# SCH.net
KiCad netlist of a schematic drawn in Altium Designer
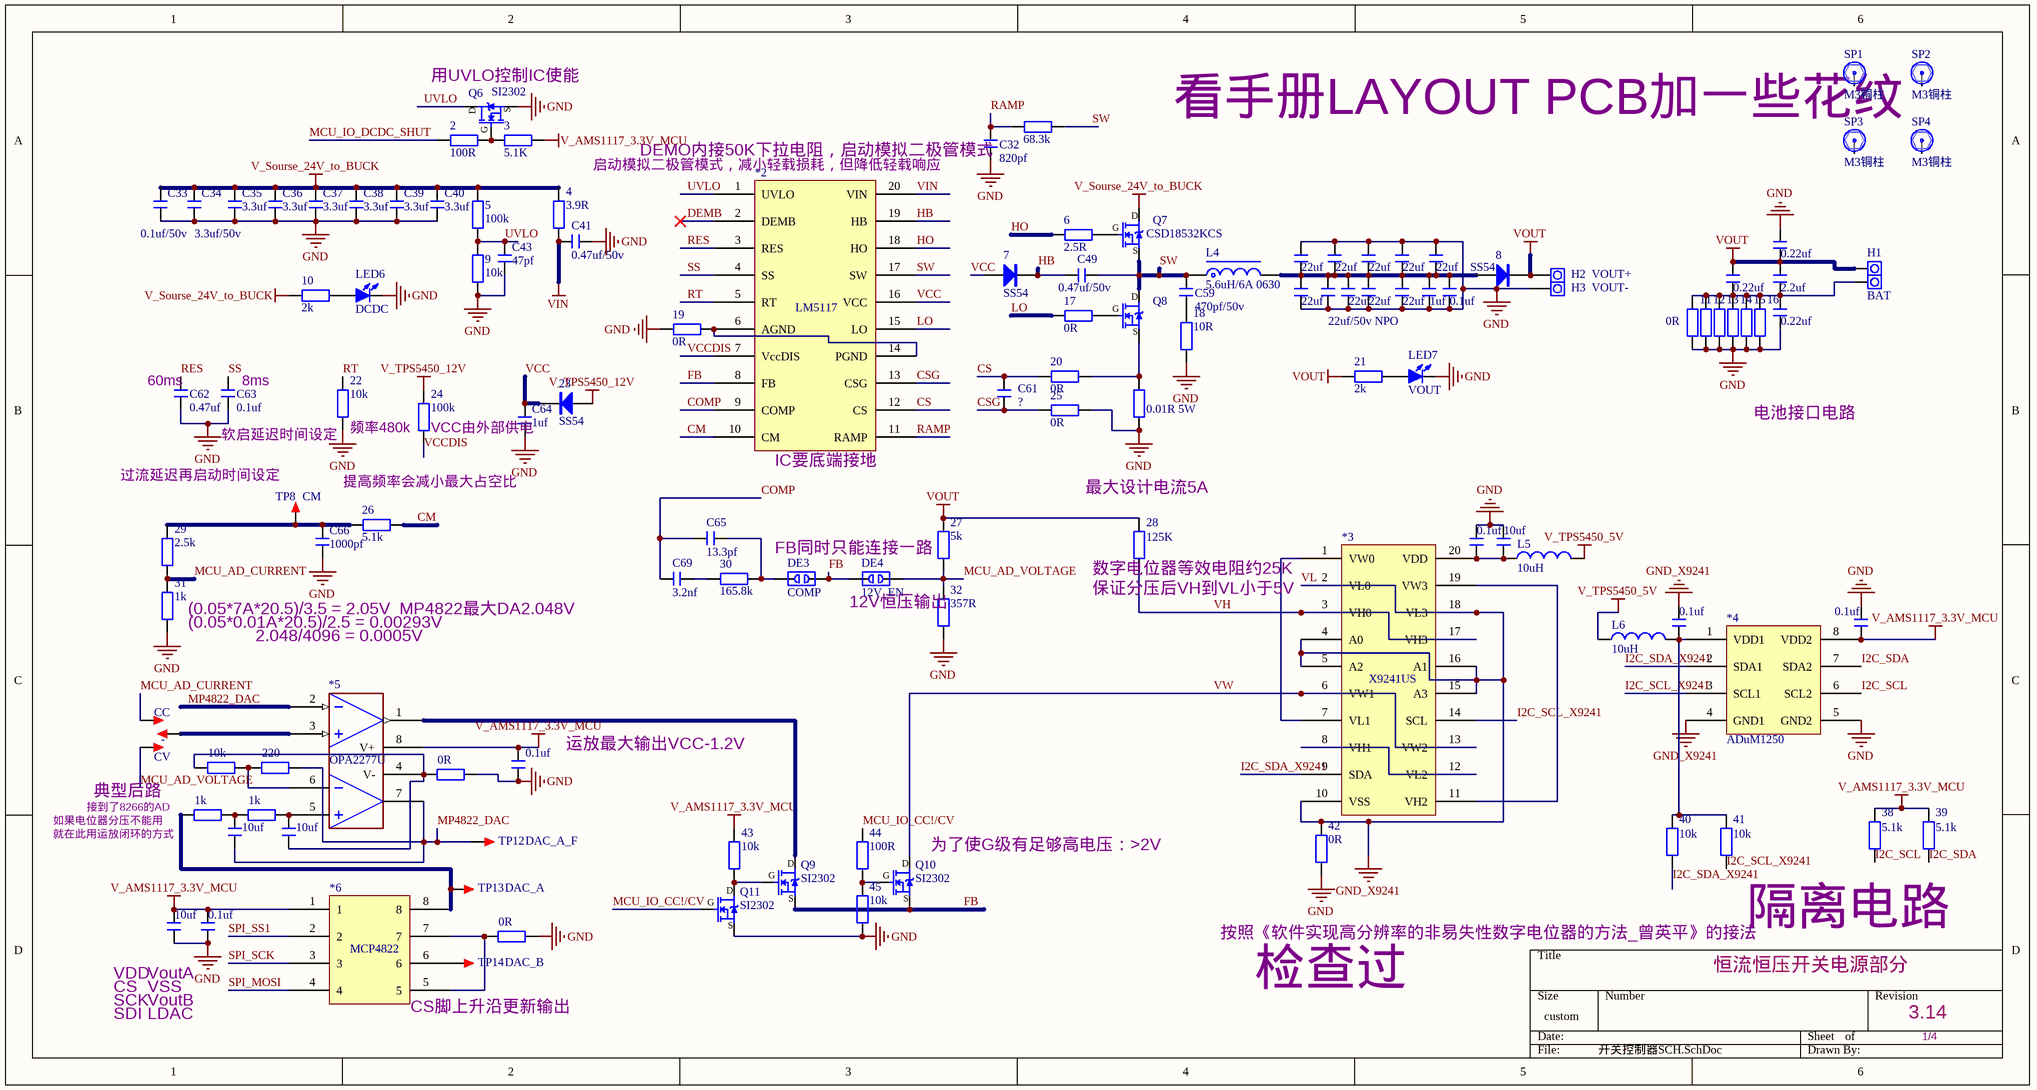
[diagram p0: 开关控制器SCH.SchDoc]

(export (version "E")
  (design (tool "Eeschema 10.0.6"))
  (components
    (comp (ref "*2") (value "LM5117") (footprint "SSOP20_M") (libsource (lib "IC_temp") (part "LM5117")))
    (comp (ref "*3") (value "X9241US") (footprint "SOP20_M") (libsource (lib "IC_temp") (part "X9241US")))
    (comp (ref "*4") (value "ADuM1250") (footprint "SOP8_N") (libsource (lib "IC_temp") (part "ADuM1250")))
    (comp (ref "*5") (value "OPA2277U") (footprint "SOP8_M") (libsource (lib "IC_temp") (part "OPA2277")))
    (comp (ref "*6") (value "MCP4822") (footprint "SOP8_M") (libsource (lib "IC_temp") (part "8")))
    (comp (ref "1")
      (value "68.3k")
      (footprint "R 0805_M")
      (description "贴片电阻")
      (libsource (lib "3.1   - 电阻-电容-电感") (part "R"))
    )
    (comp (ref "2")
      (value "100R")
      (footprint "R 0805_M")
      (description "贴片电阻")
      (libsource (lib "3.1   - 电阻-电容-电感") (part "R"))
    )
    (comp (ref "3")
      (value "5.1K")
      (footprint "R 0805_M")
      (description "贴片电阻")
      (libsource (lib "3.1   - 电阻-电容-电感") (part "R"))
    )
    (comp (ref "4")
      (value "3.9R")
      (footprint "R 0805_M")
      (description "贴片电阻")
      (libsource (lib "3.1   - 电阻-电容-电感") (part "R"))
    )
    (comp (ref "5")
      (value "100k")
      (footprint "R 0805_M")
      (description "贴片电阻")
      (libsource (lib "3.1   - 电阻-电容-电感") (part "R"))
    )
    (comp (ref "6")
      (value "2.5R")
      (footprint "R 0805_M")
      (description "贴片电阻")
      (libsource (lib "3.1   - 电阻-电容-电感") (part "R"))
    )
    (comp (ref "7")
      (value "SS54")
      (footprint "SMA")
      (description "肖特基二极管")
      (libsource (lib "8.1   - 二极管-整流桥") (part "SS34"))
    )
    (comp (ref "8")
      (value "SS54")
      (footprint "SMA")
      (description "肖特基二极管")
      (libsource (lib "8.1   - 二极管-整流桥") (part "SS34"))
    )
    (comp (ref "9")
      (value "10k")
      (footprint "R 0805_M")
      (description "贴片电阻")
      (libsource (lib "3.1   - 电阻-电容-电感") (part "R"))
    )
    (comp (ref "10")
      (value "2k")
      (footprint "R 0805_M")
      (description "贴片电阻")
      (libsource (lib "3.1   - 电阻-电容-电感") (part "R"))
    )
    (comp (ref "11")
      (value "0R")
      (footprint "R 0805_M")
      (description "贴片电阻")
      (libsource (lib "3.1   - 电阻-电容-电感") (part "R"))
    )
    (comp (ref "12")
      (value "0R")
      (footprint "R 0805_M")
      (description "贴片电阻")
      (libsource (lib "3.1   - 电阻-电容-电感") (part "R"))
    )
    (comp (ref "13")
      (value "0R")
      (footprint "R 0805_M")
      (description "贴片电阻")
      (libsource (lib "3.1   - 电阻-电容-电感") (part "R"))
    )
    (comp (ref "14")
      (value "0R")
      (footprint "R 0805_M")
      (description "贴片电阻")
      (libsource (lib "3.1   - 电阻-电容-电感") (part "R"))
    )
    (comp (ref "15")
      (value "0R")
      (footprint "R 0805_M")
      (description "贴片电阻")
      (libsource (lib "3.1   - 电阻-电容-电感") (part "R"))
    )
    (comp (ref "16")
      (value "0R")
      (footprint "R 0805_M")
      (description "贴片电阻")
      (libsource (lib "3.1   - 电阻-电容-电感") (part "R"))
    )
    (comp (ref "17")
      (value "0R")
      (footprint "R 0805_M")
      (description "贴片电阻")
      (libsource (lib "3.1   - 电阻-电容-电感") (part "R"))
    )
    (comp (ref "18")
      (value "10R")
      (footprint "R 0805_M")
      (description "贴片电阻")
      (libsource (lib "3.1   - 电阻-电容-电感") (part "R"))
    )
    (comp (ref "19")
      (value "0R")
      (footprint "R 0805_M")
      (description "贴片电阻")
      (libsource (lib "3.1   - 电阻-电容-电感") (part "R"))
    )
    (comp (ref "20")
      (value "0R")
      (footprint "R 0805_M")
      (description "贴片电阻")
      (libsource (lib "3.1   - 电阻-电容-电感") (part "R"))
    )
    (comp (ref "21")
      (value "2k")
      (footprint "R 0805_M")
      (description "贴片电阻")
      (libsource (lib "3.1   - 电阻-电容-电感") (part "R"))
    )
    (comp (ref "22")
      (value "10k")
      (footprint "R 0805_M")
      (description "贴片电阻")
      (libsource (lib "3.1   - 电阻-电容-电感") (part "R"))
    )
    (comp (ref "23")
      (value "SS54")
      (footprint "SMA")
      (description "肖特基二极管")
      (libsource (lib "8.1   - 二极管-整流桥") (part "SS34"))
    )
    (comp (ref "24")
      (value "100k")
      (footprint "R 0805_M")
      (description "贴片电阻")
      (libsource (lib "3.1   - 电阻-电容-电感") (part "R"))
    )
    (comp (ref "25")
      (value "0R")
      (footprint "R 0805_M")
      (description "贴片电阻")
      (libsource (lib "3.1   - 电阻-电容-电感") (part "R"))
    )
    (comp (ref "26")
      (value "5.1k")
      (footprint "R 0805_M")
      (description "贴片电阻")
      (libsource (lib "3.1   - 电阻-电容-电感") (part "R"))
    )
    (comp (ref "27")
      (value "5k")
      (footprint "R 0805_M")
      (description "贴片电阻")
      (libsource (lib "3.1   - 电阻-电容-电感") (part "R"))
    )
    (comp (ref "28")
      (value "125K")
      (footprint "R 0805_M")
      (description "贴片电阻")
      (libsource (lib "3.1   - 电阻-电容-电感") (part "R"))
    )
    (comp (ref "29")
      (value "2.5k")
      (footprint "R 0805_M")
      (description "贴片电阻")
      (libsource (lib "3.1   - 电阻-电容-电感") (part "R"))
    )
    (comp (ref "30")
      (value "165.8k")
      (footprint "R 0805_M")
      (description "贴片电阻")
      (libsource (lib "3.1   - 电阻-电容-电感") (part "R"))
    )
    (comp (ref "31")
      (value "1k")
      (footprint "R 0805_M")
      (description "贴片电阻")
      (libsource (lib "3.1   - 电阻-电容-电感") (part "R"))
    )
    (comp (ref "32")
      (value "357R")
      (footprint "R 0805_M")
      (description "贴片电阻")
      (libsource (lib "3.1   - 电阻-电容-电感") (part "R"))
    )
    (comp (ref "33")
      (value "10k")
      (footprint "R 0805_M")
      (description "贴片电阻")
      (libsource (lib "3.1   - 电阻-电容-电感") (part "R"))
    )
    (comp (ref "34")
      (value "220")
      (footprint "R 0805_M")
      (description "贴片电阻")
      (libsource (lib "3.1   - 电阻-电容-电感") (part "R"))
    )
    (comp (ref "35")
      (value "0R")
      (footprint "R 0805_M")
      (description "贴片电阻")
      (libsource (lib "3.1   - 电阻-电容-电感") (part "R"))
    )
    (comp (ref "36")
      (value "1k")
      (footprint "R 0805_M")
      (description "贴片电阻")
      (libsource (lib "3.1   - 电阻-电容-电感") (part "R"))
    )
    (comp (ref "37")
      (value "1k")
      (footprint "R 0805_M")
      (description "贴片电阻")
      (libsource (lib "3.1   - 电阻-电容-电感") (part "R"))
    )
    (comp (ref "38")
      (value "5.1k")
      (footprint "R 0805_M")
      (description "贴片电阻")
      (libsource (lib "3.1   - 电阻-电容-电感") (part "R"))
    )
    (comp (ref "39")
      (value "5.1k")
      (footprint "R 0805_M")
      (description "贴片电阻")
      (libsource (lib "3.1   - 电阻-电容-电感") (part "R"))
    )
    (comp (ref "40")
      (value "10k")
      (footprint "R 0805_M")
      (description "贴片电阻")
      (libsource (lib "3.1   - 电阻-电容-电感") (part "R"))
    )
    (comp (ref "41")
      (value "10k")
      (footprint "R 0805_M")
      (description "贴片电阻")
      (libsource (lib "3.1   - 电阻-电容-电感") (part "R"))
    )
    (comp (ref "42")
      (value "0R")
      (footprint "R 0805_M")
      (description "贴片电阻")
      (libsource (lib "3.1   - 电阻-电容-电感") (part "R"))
    )
    (comp (ref "43")
      (value "10k")
      (footprint "R 0805_M")
      (description "贴片电阻")
      (libsource (lib "3.1   - 电阻-电容-电感") (part "R"))
    )
    (comp (ref "44")
      (value "100R")
      (footprint "R 0805_M")
      (description "贴片电阻")
      (libsource (lib "3.1   - 电阻-电容-电感") (part "R"))
    )
    (comp (ref "45")
      (value "10k")
      (footprint "R 0805_M")
      (description "贴片电阻")
      (libsource (lib "3.1   - 电阻-电容-电感") (part "R"))
    )
    (comp (ref "46")
      (value "0R")
      (footprint "R 0805_M")
      (description "贴片电阻")
      (libsource (lib "3.1   - 电阻-电容-电感") (part "R"))
    )
    (comp (ref "C32")
      (value "820pf")
      (footprint "C 0805_M")
      (description "无极性贴片电容")
      (libsource (lib "3.1   - 电阻-电容-电感") (part "C"))
    )
    (comp (ref "C33")
      (value "0.1uf/50v")
      (footprint "C 0805_M")
      (description "无极性贴片电容")
      (libsource (lib "3.1   - 电阻-电容-电感") (part "C"))
    )
    (comp (ref "C34")
      (value "3.3uf/50v")
      (footprint "C 0805_M")
      (description "无极性贴片电容")
      (libsource (lib "3.1   - 电阻-电容-电感") (part "C"))
    )
    (comp (ref "C35")
      (value "3.3uf")
      (footprint "C 0805_M")
      (description "无极性贴片电容")
      (libsource (lib "3.1   - 电阻-电容-电感") (part "C"))
    )
    (comp (ref "C36")
      (value "3.3uf")
      (footprint "C 0805_M")
      (description "无极性贴片电容")
      (libsource (lib "3.1   - 电阻-电容-电感") (part "C"))
    )
    (comp (ref "C37")
      (value "3.3uf")
      (footprint "C 0805_M")
      (description "无极性贴片电容")
      (libsource (lib "3.1   - 电阻-电容-电感") (part "C"))
    )
    (comp (ref "C38")
      (value "3.3uf")
      (footprint "C 0805_M")
      (description "无极性贴片电容")
      (libsource (lib "3.1   - 电阻-电容-电感") (part "C"))
    )
    (comp (ref "C39")
      (value "3.3uf")
      (footprint "C 0805_M")
      (description "无极性贴片电容")
      (libsource (lib "3.1   - 电阻-电容-电感") (part "C"))
    )
    (comp (ref "C40")
      (value "3.3uf")
      (footprint "C 0805_M")
      (description "无极性贴片电容")
      (libsource (lib "3.1   - 电阻-电容-电感") (part "C"))
    )
    (comp (ref "C41")
      (value "0.47uf/50v")
      (footprint "C 0805_M")
      (description "无极性贴片电容")
      (libsource (lib "3.1   - 电阻-电容-电感") (part "C"))
    )
    (comp (ref "C42")
      (value "0.22uf")
      (footprint "C 0805_M")
      (description "无极性贴片电容")
      (libsource (lib "3.1   - 电阻-电容-电感") (part "C"))
    )
    (comp (ref "C43")
      (value "47pf")
      (footprint "C 0805_M")
      (description "无极性贴片电容")
      (libsource (lib "3.1   - 电阻-电容-电感") (part "C"))
    )
    (comp (ref "C44")
      (value "22uf")
      (footprint "C 0805_M")
      (description "无极性贴片电容")
      (libsource (lib "3.1   - 电阻-电容-电感") (part "C"))
    )
    (comp (ref "C45")
      (value "22uf")
      (footprint "C 0805_M")
      (description "无极性贴片电容")
      (libsource (lib "3.1   - 电阻-电容-电感") (part "C"))
    )
    (comp (ref "C46")
      (value "22uf")
      (footprint "C 0805_M")
      (description "无极性贴片电容")
      (libsource (lib "3.1   - 电阻-电容-电感") (part "C"))
    )
    (comp (ref "C47")
      (value "22uf")
      (footprint "C 0805_M")
      (description "无极性贴片电容")
      (libsource (lib "3.1   - 电阻-电容-电感") (part "C"))
    )
    (comp (ref "C48")
      (value "22uf")
      (footprint "C 0805_M")
      (description "无极性贴片电容")
      (libsource (lib "3.1   - 电阻-电容-电感") (part "C"))
    )
    (comp (ref "C49")
      (value "0.47uf/50v")
      (footprint "C 0805_M")
      (description "无极性贴片电容")
      (libsource (lib "3.1   - 电阻-电容-电感") (part "C"))
    )
    (comp (ref "C50")
      (value "0.22uf")
      (footprint "C 0805_M")
      (description "无极性贴片电容")
      (libsource (lib "3.1   - 电阻-电容-电感") (part "C"))
    )
    (comp (ref "C51")
      (value "2.2uf")
      (footprint "C 0805_M")
      (description "无极性贴片电容")
      (libsource (lib "3.1   - 电阻-电容-电感") (part "C"))
    )
    (comp (ref "C52")
      (value "22uf")
      (footprint "C 0805_M")
      (description "无极性贴片电容")
      (libsource (lib "3.1   - 电阻-电容-电感") (part "C"))
    )
    (comp (ref "C53")
      (value "22uf/50v NPO")
      (footprint "C 0805_M")
      (description "无极性贴片电容")
      (libsource (lib "3.1   - 电阻-电容-电感") (part "C"))
    )
    (comp (ref "C54")
      (value "22uf")
      (footprint "C 0805_M")
      (description "无极性贴片电容")
      (libsource (lib "3.1   - 电阻-电容-电感") (part "C"))
    )
    (comp (ref "C55")
      (value "22uf")
      (footprint "C 0805_M")
      (description "无极性贴片电容")
      (libsource (lib "3.1   - 电阻-电容-电感") (part "C"))
    )
    (comp (ref "C56")
      (value "22uf")
      (footprint "C 0805_M")
      (description "无极性贴片电容")
      (libsource (lib "3.1   - 电阻-电容-电感") (part "C"))
    )
    (comp (ref "C57")
      (value "1uf")
      (footprint "C 0805_M")
      (description "无极性贴片电容")
      (libsource (lib "3.1   - 电阻-电容-电感") (part "C"))
    )
    (comp (ref "C58")
      (value "0.1uf")
      (footprint "C 0805_M")
      (description "无极性贴片电容")
      (libsource (lib "3.1   - 电阻-电容-电感") (part "C"))
    )
    (comp (ref "C59")
      (value "470pf/50v")
      (footprint "C 0805_M")
      (description "无极性贴片电容")
      (libsource (lib "3.1   - 电阻-电容-电感") (part "C"))
    )
    (comp (ref "C60")
      (value "0.22uf")
      (footprint "C 0805_M")
      (description "无极性贴片电容")
      (libsource (lib "3.1   - 电阻-电容-电感") (part "C"))
    )
    (comp (ref "C61")
      (value "?")
      (footprint "C 0805_M")
      (description "无极性贴片电容")
      (libsource (lib "3.1   - 电阻-电容-电感") (part "C"))
    )
    (comp (ref "C62")
      (value "0.47uf")
      (footprint "C 0805_M")
      (description "无极性贴片电容")
      (libsource (lib "3.1   - 电阻-电容-电感") (part "C"))
    )
    (comp (ref "C63")
      (value "0.1uf")
      (footprint "C 0805_M")
      (description "无极性贴片电容")
      (libsource (lib "3.1   - 电阻-电容-电感") (part "C"))
    )
    (comp (ref "C64")
      (value "1uf")
      (footprint "C 0805_M")
      (description "无极性贴片电容")
      (libsource (lib "3.1   - 电阻-电容-电感") (part "C"))
    )
    (comp (ref "C65")
      (value "13.3pf")
      (footprint "C 0805_M")
      (description "无极性贴片电容")
      (libsource (lib "3.1   - 电阻-电容-电感") (part "C"))
    )
    (comp (ref "C66")
      (value "1000pf")
      (footprint "C 0805_M")
      (description "无极性贴片电容")
      (libsource (lib "3.1   - 电阻-电容-电感") (part "C"))
    )
    (comp (ref "C67")
      (value "0.1uf")
      (footprint "C 0805_M")
      (description "无极性贴片电容")
      (libsource (lib "3.1   - 电阻-电容-电感") (part "C"))
    )
    (comp (ref "C68")
      (value "10uf")
      (footprint "C 0805_M")
      (description "无极性贴片电容")
      (libsource (lib "3.1   - 电阻-电容-电感") (part "C"))
    )
    (comp (ref "C69")
      (value "3.2nf")
      (footprint "C 0805_M")
      (description "无极性贴片电容")
      (libsource (lib "3.1   - 电阻-电容-电感") (part "C"))
    )
    (comp (ref "C70")
      (value "0.1uf")
      (footprint "C 0805_M")
      (description "无极性贴片电容")
      (libsource (lib "3.1   - 电阻-电容-电感") (part "C"))
    )
    (comp (ref "C71")
      (value "0.1uf")
      (footprint "C 0805_M")
      (description "无极性贴片电容")
      (libsource (lib "3.1   - 电阻-电容-电感") (part "C"))
    )
    (comp (ref "C72")
      (value "0.1uf")
      (footprint "C 0805_M")
      (description "无极性贴片电容")
      (libsource (lib "3.1   - 电阻-电容-电感") (part "C"))
    )
    (comp (ref "C73")
      (value "10uf")
      (footprint "C 0805_M")
      (description "无极性贴片电容")
      (libsource (lib "3.1   - 电阻-电容-电感") (part "C"))
    )
    (comp (ref "C74")
      (value "10uf")
      (footprint "C 0805_M")
      (description "无极性贴片电容")
      (libsource (lib "3.1   - 电阻-电容-电感") (part "C"))
    )
    (comp (ref "C75")
      (value "10uf")
      (footprint "C 0805_M")
      (description "无极性贴片电容")
      (libsource (lib "3.1   - 电阻-电容-电感") (part "C"))
    )
    (comp (ref "C76")
      (value "0.1uf")
      (footprint "C 0805_M")
      (description "无极性贴片电容")
      (libsource (lib "3.1   - 电阻-电容-电感") (part "C"))
    )
    (comp (ref "DE3")
      (value "COMP")
      (footprint "DEBUG_B")
      (description "调试断点焊盘")
      (libsource (lib "15.1 - 未分类器件") (part "DEBUG"))
    )
    (comp (ref "DE4")
      (value "12V_EN")
      (footprint "DEBUG_B")
      (description "调试断点焊盘")
      (libsource (lib "15.1 - 未分类器件") (part "DEBUG"))
    )
    (comp (ref "H1")
      (value "BAT")
      (footprint "T_head")
      (description "引线焊盘")
      (libsource (lib "15.1 - 未分类器件") (part "PAD2"))
    )
    (comp (ref "H2")
      (value "VOUT+")
      (footprint "PAD1-SMD-C")
      (description "引线焊盘")
      (libsource (lib "15.1 - 未分类器件") (part "PAD1"))
    )
    (comp (ref "H3")
      (value "VOUT-")
      (footprint "PAD1-SMD-C")
      (description "引线焊盘")
      (libsource (lib "15.1 - 未分类器件") (part "PAD1"))
    )
    (comp (ref "L4")
      (value "5.6uH/6A 0630")
      (footprint "L-SMD-0630")
      (description "功率屏蔽电感")
      (libsource (lib "3.1   - 电阻-电容-电感") (part "L-CDRH"))
    )
    (comp (ref "L5")
      (value "10uH")
      (footprint "L 0805_M")
      (description "小功率贴片电感")
      (libsource (lib "3.1   - 电阻-电容-电感") (part "L"))
    )
    (comp (ref "L6")
      (value "10uH")
      (footprint "L 0805_M")
      (description "小功率贴片电感")
      (libsource (lib "3.1   - 电阻-电容-电感") (part "L"))
    )
    (comp (ref "LED6")
      (value "DCDC")
      (footprint "LED 0805G")
      (description "贴片LED")
      (libsource (lib "9.1   - LED") (part "LED-SMD"))
    )
    (comp (ref "LED7")
      (value "VOUT")
      (footprint "LED 0805G")
      (description "贴片LED")
      (libsource (lib "9.1   - LED") (part "LED-SMD"))
    )
    (comp (ref "Q6")
      (value "SI2302")
      (footprint "SOT23-3N")
      (description "N沟道 20V/3A")
      (libsource (lib "6.1   - 场效应管-可控硅") (part "SI2302"))
    )
    (comp (ref "Q7")
      (value "CSD18532KCS")
      (footprint "TO220A")
      (libsource (lib "6.1   - 场效应管-可控硅") (part "2SK3615"))
    )
    (comp (ref "Q8")
      (value "CSD18532KCS")
      (footprint "TO220A")
      (libsource (lib "6.1   - 场效应管-可控硅") (part "2SK3615"))
    )
    (comp (ref "Q9")
      (value "SI2302")
      (footprint "SOT23-3N")
      (description "N沟道 20V/3A")
      (libsource (lib "6.1   - 场效应管-可控硅") (part "SI2302"))
    )
    (comp (ref "Q10")
      (value "SI2302")
      (footprint "SOT23-3N")
      (description "N沟道 20V/3A")
      (libsource (lib "6.1   - 场效应管-可控硅") (part "SI2302"))
    )
    (comp (ref "Q11")
      (value "SI2302")
      (footprint "SOT23-3N")
      (description "N沟道 20V/3A")
      (libsource (lib "6.1   - 场效应管-可控硅") (part "SI2302"))
    )
    (comp (ref "R68")
      (value "0.01R 5W")
      (footprint "RS 3W-V7")
      (description "直插色环电阻")
      (libsource (lib "3.1   - 电阻-电容-电感") (part "R-CRR"))
    )
    (comp (ref "SP1")
      (value "M3铜柱")
      (footprint "M3x4+6_N")
      (description "铜柱")
      (libsource (lib "15.1 - 未分类器件") (part "铜柱加头大焊盘"))
    )
    (comp (ref "SP2")
      (value "M3铜柱")
      (footprint "M3x4+6_N")
      (description "铜柱")
      (libsource (lib "15.1 - 未分类器件") (part "铜柱加头大焊盘"))
    )
    (comp (ref "SP3")
      (value "M3铜柱")
      (footprint "M3x4+6_N")
      (description "铜柱")
      (libsource (lib "15.1 - 未分类器件") (part "铜柱加头大焊盘"))
    )
    (comp (ref "SP4")
      (value "M3铜柱")
      (footprint "M3x4+6_N")
      (description "铜柱")
      (libsource (lib "15.1 - 未分类器件") (part "铜柱加头大焊盘"))
    )
    (comp (ref "TP8")
      (value "CM")
      (footprint "TEST 1")
      (description "测试点")
      (libsource (lib "15.1 - 未分类器件") (part "TEST"))
    )
    (comp (ref "TP9")
      (value "CC")
      (footprint "TEST 1")
      (description "测试点")
      (libsource (lib "15.1 - 未分类器件") (part "TEST"))
    )
    (comp (ref "TP10")
      (value "-")
      (footprint "TEST 1")
      (description "测试点")
      (libsource (lib "15.1 - 未分类器件") (part "TEST"))
    )
    (comp (ref "TP11")
      (value "CV")
      (footprint "TEST 1")
      (description "测试点")
      (libsource (lib "15.1 - 未分类器件") (part "TEST"))
    )
    (comp (ref "TP12")
      (value "DAC_A_F")
      (footprint "TEST 1")
      (description "测试点")
      (libsource (lib "15.1 - 未分类器件") (part "TEST"))
    )
    (comp (ref "TP13")
      (value "DAC_A")
      (footprint "TEST 1")
      (description "测试点")
      (libsource (lib "15.1 - 未分类器件") (part "TEST"))
    )
    (comp (ref "TP14")
      (value "DAC_B")
      (footprint "TEST 1")
      (description "测试点")
      (libsource (lib "15.1 - 未分类器件") (part "TEST"))
    )
  )
  (nets
    (net (code "1") (name "/CM") (class "Default")
      (node (ref "*2") (pin "10") (pinfunction "CM_10") (pintype "passive"))
      (node (ref "26") (pin "2") (pinfunction "2_2") (pintype "passive"))
    )
    (net (code "2") (name "/COMP") (class "Default")
      (node (ref "*2") (pin "9") (pinfunction "COMP_9") (pintype "passive"))
      (node (ref "C65") (pin "1") (pinfunction "1_1") (pintype "passive"))
      (node (ref "C69") (pin "1") (pinfunction "1_1") (pintype "passive"))
    )
    (net (code "3") (name "/CS") (class "Default")
      (node (ref "*2") (pin "12") (pinfunction "CS_12") (pintype "passive"))
      (node (ref "20") (pin "2") (pinfunction "2_2") (pintype "passive"))
      (node (ref "C61") (pin "1") (pinfunction "1_1") (pintype "passive"))
    )
    (net (code "4") (name "/CSG") (class "Default")
      (node (ref "*2") (pin "13") (pinfunction "CSG_13") (pintype "passive"))
      (node (ref "25") (pin "2") (pinfunction "2_2") (pintype "passive"))
      (node (ref "C61") (pin "2") (pinfunction "2_2") (pintype "passive"))
    )
    (net (code "5") (name "/DEMB") (class "Default")
      (node (ref "*2") (pin "2") (pinfunction "DEMB_2") (pintype "passive+no_connect"))
    )
    (net (code "6") (name "/FB") (class "Default")
      (node (ref "*2") (pin "8") (pinfunction "FB_8") (pintype "passive"))
      (node (ref "DE3") (pin "2") (pinfunction "2_2") (pintype "passive"))
      (node (ref "DE4") (pin "1") (pinfunction "1_1") (pintype "passive"))
      (node (ref "Q10") (pin "2") (pinfunction "S_2") (pintype "passive"))
      (node (ref "Q9") (pin "2") (pinfunction "S_2") (pintype "passive"))
    )
    (net (code "7") (name "/HB") (class "Default")
      (node (ref "*2") (pin "19") (pinfunction "HB_19") (pintype "passive"))
      (node (ref "7") (pin "2") (pinfunction "K_2") (pintype "passive"))
      (node (ref "C49") (pin "2") (pinfunction "2_2") (pintype "passive"))
    )
    (net (code "8") (name "/HO") (class "Default")
      (node (ref "*2") (pin "18") (pinfunction "HO_18") (pintype "passive"))
      (node (ref "6") (pin "2") (pinfunction "2_2") (pintype "passive"))
    )
    (net (code "9") (name "/I2C_SCL") (class "Default")
      (node (ref "*4") (pin "6") (pinfunction "SCL2_6") (pintype "power_in"))
      (node (ref "38") (pin "2") (pinfunction "2_2") (pintype "passive"))
    )
    (net (code "10") (name "/I2C_SCL_X9241") (class "Default")
      (node (ref "*3") (pin "14") (pinfunction "SCL_14") (pintype "passive"))
      (node (ref "*4") (pin "3") (pinfunction "SCL1_3") (pintype "power_in"))
      (node (ref "41") (pin "2") (pinfunction "2_2") (pintype "passive"))
    )
    (net (code "11") (name "/I2C_SDA") (class "Default")
      (node (ref "*4") (pin "7") (pinfunction "SDA2_7") (pintype "power_in"))
      (node (ref "39") (pin "2") (pinfunction "2_2") (pintype "passive"))
    )
    (net (code "12") (name "/I2C_SDA_X9241") (class "Default")
      (node (ref "*3") (pin "9") (pinfunction "SDA_9") (pintype "passive"))
      (node (ref "*4") (pin "2") (pinfunction "SDA1_2") (pintype "power_in"))
      (node (ref "40") (pin "2") (pinfunction "2_2") (pintype "passive"))
    )
    (net (code "13") (name "/LO") (class "Default")
      (node (ref "*2") (pin "15") (pinfunction "LO_15") (pintype "passive"))
      (node (ref "17") (pin "2") (pinfunction "2_2") (pintype "passive"))
    )
    (net (code "14") (name "/MCU_AD_CURRENT") (class "Default")
      (node (ref "29") (pin "1") (pinfunction "1_1") (pintype "passive"))
      (node (ref "31") (pin "2") (pinfunction "2_2") (pintype "passive"))
      (node (ref "TP9") (pin "1") (pinfunction "1_1") (pintype "passive"))
    )
    (net (code "15") (name "/MCU_AD_VOLTAGE") (class "Default")
      (node (ref "27") (pin "2") (pinfunction "2_2") (pintype "passive"))
      (node (ref "32") (pin "1") (pinfunction "1_1") (pintype "passive"))
      (node (ref "DE4") (pin "2") (pinfunction "2_2") (pintype "passive"))
      (node (ref "TP11") (pin "1") (pinfunction "1_1") (pintype "passive"))
    )
    (net (code "16") (name "/MCU_IO_CC!{slash}CV") (class "Default")
      (node (ref "44") (pin "1") (pinfunction "1_1") (pintype "passive"))
      (node (ref "Q11") (pin "1") (pinfunction "G_1") (pintype "passive"))
    )
    (net (code "17") (name "/MCU_IO_DCDC_SHUT") (class "Default")
      (node (ref "2") (pin "2") (pinfunction "2_2") (pintype "passive"))
    )
    (net (code "18") (name "/MP4822_DAC") (class "Default")
      (node (ref "*5") (pin "2") (pinfunction "In_A-_2") (pintype "input"))
      (node (ref "*5") (pin "7") (pinfunction "Out_B_7") (pintype "power_in"))
      (node (ref "34") (pin "1") (pinfunction "1_1") (pintype "passive"))
      (node (ref "C73") (pin "1") (pinfunction "1_1") (pintype "passive"))
      (node (ref "TP12") (pin "1") (pinfunction "1_1") (pintype "passive"))
    )
    (net (code "19") (name "/RAMP") (class "Default")
      (node (ref "*2") (pin "11") (pinfunction "RAMP_11") (pintype "passive"))
      (node (ref "1") (pin "2") (pinfunction "2_2") (pintype "passive"))
      (node (ref "C32") (pin "1") (pinfunction "1_1") (pintype "passive"))
    )
    (net (code "20") (name "/RES") (class "Default")
      (node (ref "*2") (pin "3") (pinfunction "RES_3") (pintype "passive"))
      (node (ref "C62") (pin "1") (pinfunction "1_1") (pintype "passive"))
    )
    (net (code "21") (name "/RT") (class "Default")
      (node (ref "*2") (pin "5") (pinfunction "RT_5") (pintype "passive"))
      (node (ref "22") (pin "1") (pinfunction "1_1") (pintype "passive"))
    )
    (net (code "22") (name "/SPI_MOSI") (class "Default")
      (node (ref "*6") (pin "4") (pinfunction "4_4") (pintype "passive"))
    )
    (net (code "23") (name "/SPI_SCK") (class "Default")
      (node (ref "*6") (pin "3") (pinfunction "3_3") (pintype "passive"))
    )
    (net (code "24") (name "/SPI_SS1") (class "Default")
      (node (ref "*6") (pin "2") (pinfunction "2_2") (pintype "passive"))
    )
    (net (code "25") (name "/SS") (class "Default")
      (node (ref "*2") (pin "4") (pinfunction "SS_4") (pintype "passive"))
      (node (ref "C63") (pin "1") (pinfunction "1_1") (pintype "passive"))
    )
    (net (code "26") (name "/SW") (class "Default")
      (node (ref "*2") (pin "17") (pinfunction "SW_17") (pintype "passive"))
      (node (ref "1") (pin "1") (pinfunction "1_1") (pintype "passive"))
      (node (ref "C49") (pin "1") (pinfunction "1_1") (pintype "passive"))
      (node (ref "C59") (pin "1") (pinfunction "1_1") (pintype "passive"))
      (node (ref "L4") (pin "1") (pinfunction "1_1") (pintype "passive"))
      (node (ref "Q7") (pin "3") (pinfunction "S_3") (pintype "passive"))
      (node (ref "Q8") (pin "2") (pinfunction "D_2") (pintype "passive"))
    )
    (net (code "27") (name "/UVLO") (class "Default")
      (node (ref "*2") (pin "1") (pinfunction "UVLO_1") (pintype "passive"))
      (node (ref "5") (pin "1") (pinfunction "1_1") (pintype "passive"))
      (node (ref "9") (pin "2") (pinfunction "2_2") (pintype "passive"))
      (node (ref "C43") (pin "2") (pinfunction "2_2") (pintype "passive"))
      (node (ref "Q6") (pin "3") (pinfunction "D_3") (pintype "passive"))
    )
    (net (code "28") (name "/VCC") (class "Default")
      (node (ref "*2") (pin "16") (pinfunction "VCC_16") (pintype "passive"))
      (node (ref "23") (pin "2") (pinfunction "K_2") (pintype "passive"))
      (node (ref "7") (pin "1") (pinfunction "A_1") (pintype "passive"))
      (node (ref "C64") (pin "2") (pinfunction "2_2") (pintype "passive"))
    )
    (net (code "29") (name "/VCCDIS") (class "Default")
      (node (ref "*2") (pin "7") (pinfunction "VccDIS_7") (pintype "passive"))
      (node (ref "24") (pin "2") (pinfunction "2_2") (pintype "passive"))
    )
    (net (code "30") (name "/VH") (class "Default")
      (node (ref "*3") (pin "17") (pinfunction "VH3_17") (pintype "passive"))
      (node (ref "*3") (pin "3") (pinfunction "VH0_3") (pintype "passive"))
      (node (ref "28") (pin "2") (pinfunction "2_2") (pintype "passive"))
    )
    (net (code "31") (name "/VW") (class "Default")
      (node (ref "*3") (pin "13") (pinfunction "VW2_13") (pintype "passive"))
      (node (ref "*3") (pin "6") (pinfunction "VW1_6") (pintype "passive"))
      (node (ref "Q10") (pin "3") (pinfunction "D_3") (pintype "passive"))
    )
    (net (code "32") (name "GND") (class "Default")
      (node (ref "*4") (pin "5") (pinfunction "GND2_5") (pintype "power_in"))
      (node (ref "11") (pin "2") (pinfunction "2_2") (pintype "passive"))
      (node (ref "12") (pin "2") (pinfunction "2_2") (pintype "passive"))
      (node (ref "13") (pin "2") (pinfunction "2_2") (pintype "passive"))
      (node (ref "14") (pin "2") (pinfunction "2_2") (pintype "passive"))
      (node (ref "15") (pin "2") (pinfunction "2_2") (pintype "passive"))
      (node (ref "16") (pin "2") (pinfunction "2_2") (pintype "passive"))
      (node (ref "18") (pin "2") (pinfunction "2_2") (pintype "passive"))
      (node (ref "19") (pin "2") (pinfunction "2_2") (pintype "passive"))
      (node (ref "22") (pin "2") (pinfunction "2_2") (pintype "passive"))
      (node (ref "25") (pin "1") (pinfunction "1_1") (pintype "passive"))
      (node (ref "31") (pin "1") (pinfunction "1_1") (pintype "passive"))
      (node (ref "32") (pin "2") (pinfunction "2_2") (pintype "passive"))
      (node (ref "35") (pin "1") (pinfunction "1_1") (pintype "passive"))
      (node (ref "42") (pin "1") (pinfunction "1_1") (pintype "passive"))
      (node (ref "45") (pin "1") (pinfunction "1_1") (pintype "passive"))
      (node (ref "46") (pin "1") (pinfunction "1_1") (pintype "passive"))
      (node (ref "9") (pin "1") (pinfunction "1_1") (pintype "passive"))
      (node (ref "C32") (pin "2") (pinfunction "2_2") (pintype "passive"))
      (node (ref "C33") (pin "1") (pinfunction "1_1") (pintype "passive"))
      (node (ref "C34") (pin "1") (pinfunction "1_1") (pintype "passive"))
      (node (ref "C35") (pin "1") (pinfunction "1_1") (pintype "passive"))
      (node (ref "C36") (pin "1") (pinfunction "1_1") (pintype "passive"))
      (node (ref "C37") (pin "1") (pinfunction "1_1") (pintype "passive"))
      (node (ref "C38") (pin "1") (pinfunction "1_1") (pintype "passive"))
      (node (ref "C39") (pin "1") (pinfunction "1_1") (pintype "passive"))
      (node (ref "C40") (pin "1") (pinfunction "1_1") (pintype "passive"))
      (node (ref "C41") (pin "1") (pinfunction "1_1") (pintype "passive"))
      (node (ref "C42") (pin "1") (pinfunction "1_1") (pintype "passive"))
      (node (ref "C43") (pin "1") (pinfunction "1_1") (pintype "passive"))
      (node (ref "C44") (pin "1") (pinfunction "1_1") (pintype "passive"))
      (node (ref "C45") (pin "1") (pinfunction "1_1") (pintype "passive"))
      (node (ref "C46") (pin "1") (pinfunction "1_1") (pintype "passive"))
      (node (ref "C47") (pin "1") (pinfunction "1_1") (pintype "passive"))
      (node (ref "C48") (pin "1") (pinfunction "1_1") (pintype "passive"))
      (node (ref "C52") (pin "2") (pinfunction "2_2") (pintype "passive"))
      (node (ref "C53") (pin "2") (pinfunction "2_2") (pintype "passive"))
      (node (ref "C54") (pin "2") (pinfunction "2_2") (pintype "passive"))
      (node (ref "C55") (pin "2") (pinfunction "2_2") (pintype "passive"))
      (node (ref "C56") (pin "2") (pinfunction "2_2") (pintype "passive"))
      (node (ref "C57") (pin "2") (pinfunction "2_2") (pintype "passive"))
      (node (ref "C58") (pin "2") (pinfunction "2_2") (pintype "passive"))
      (node (ref "C60") (pin "2") (pinfunction "2_2") (pintype "passive"))
      (node (ref "C62") (pin "2") (pinfunction "2_2") (pintype "passive"))
      (node (ref "C63") (pin "2") (pinfunction "2_2") (pintype "passive"))
      (node (ref "C64") (pin "1") (pinfunction "1_1") (pintype "passive"))
      (node (ref "C66") (pin "1") (pinfunction "1_1") (pintype "passive"))
      (node (ref "C67") (pin "2") (pinfunction "2_2") (pintype "passive"))
      (node (ref "C68") (pin "2") (pinfunction "2_2") (pintype "passive"))
      (node (ref "C71") (pin "2") (pinfunction "2_2") (pintype "passive"))
      (node (ref "C72") (pin "1") (pinfunction "1_1") (pintype "passive"))
      (node (ref "C75") (pin "1") (pinfunction "1_1") (pintype "passive"))
      (node (ref "C76") (pin "1") (pinfunction "1_1") (pintype "passive"))
      (node (ref "H3") (pin "1") (pinfunction "1_1") (pintype "passive"))
      (node (ref "LED6") (pin "2") (pinfunction "K_2") (pintype "passive"))
      (node (ref "LED7") (pin "2") (pinfunction "K_2") (pintype "passive"))
      (node (ref "Q11") (pin "2") (pinfunction "S_2") (pintype "passive"))
      (node (ref "Q6") (pin "2") (pinfunction "S_2") (pintype "passive"))
      (node (ref "R68") (pin "1") (pinfunction "1_1") (pintype "passive"))
    )
    (net (code "33") (name "GND_X9241") (class "Default")
      (node (ref "*3") (pin "10") (pinfunction "VSS_10") (pintype "passive"))
      (node (ref "*3") (pin "15") (pinfunction "A3_15") (pintype "passive"))
      (node (ref "*3") (pin "16") (pinfunction "A1_16") (pintype "passive"))
      (node (ref "*3") (pin "18") (pinfunction "VL3_18") (pintype "passive"))
      (node (ref "*3") (pin "2") (pinfunction "VL0_2") (pintype "passive"))
      (node (ref "*3") (pin "4") (pinfunction "A0_4") (pintype "passive"))
      (node (ref "*3") (pin "5") (pinfunction "A2_5") (pintype "passive"))
      (node (ref "*4") (pin "4") (pinfunction "GND1_4") (pintype "power_in"))
      (node (ref "42") (pin "2") (pinfunction "2_2") (pintype "passive"))
      (node (ref "C70") (pin "2") (pinfunction "2_2") (pintype "passive"))
    )
    (net (code "34") (name "Net-(*2-AGND)") (class "Default")
      (node (ref "*2") (pin "14") (pinfunction "PGND_14") (pintype "passive"))
      (node (ref "*2") (pin "6") (pinfunction "AGND_6") (pintype "passive"))
      (node (ref "19") (pin "1") (pinfunction "1_1") (pintype "passive"))
    )
    (net (code "35") (name "Net-(*3-VDD)") (class "Default")
      (node (ref "*3") (pin "20") (pinfunction "VDD_20") (pintype "passive"))
      (node (ref "C67") (pin "1") (pinfunction "1_1") (pintype "passive"))
      (node (ref "C68") (pin "1") (pinfunction "1_1") (pintype "passive"))
      (node (ref "L5") (pin "1") (pinfunction "1_1") (pintype "passive"))
    )
    (net (code "36") (name "Net-(*3-VH1)") (class "Default")
      (node (ref "*3") (pin "12") (pinfunction "VL2_12") (pintype "passive"))
      (node (ref "*3") (pin "8") (pinfunction "VH1_8") (pintype "passive"))
    )
    (net (code "37") (name "Net-(*3-VH2)") (class "Default")
      (node (ref "*3") (pin "11") (pinfunction "VH2_11") (pintype "passive"))
      (node (ref "*3") (pin "19") (pinfunction "VW3_19") (pintype "passive"))
    )
    (net (code "38") (name "Net-(*3-VL1)") (class "Default")
      (node (ref "*3") (pin "1") (pinfunction "VW0_1") (pintype "passive"))
      (node (ref "*3") (pin "7") (pinfunction "VL1_7") (pintype "passive"))
    )
    (net (code "39") (name "Net-(*4-VDD1)") (class "Default")
      (node (ref "*4") (pin "1") (pinfunction "VDD1_1") (pintype "power_in"))
      (node (ref "40") (pin "1") (pinfunction "1_1") (pintype "passive"))
      (node (ref "41") (pin "1") (pinfunction "1_1") (pintype "passive"))
      (node (ref "C70") (pin "1") (pinfunction "1_1") (pintype "passive"))
      (node (ref "L6") (pin "2") (pinfunction "2_2") (pintype "passive"))
    )
    (net (code "40") (name "Net-(*5-In_A+)") (class "Default")
      (node (ref "*5") (pin "3") (pinfunction "In_A+_3") (pintype "input"))
      (node (ref "TP10") (pin "1") (pinfunction "1_1") (pintype "passive"))
    )
    (net (code "41") (name "Net-(*5-In_B+)") (class "Default")
      (node (ref "*5") (pin "5") (pinfunction "In_B+_5") (pintype "power_in"))
      (node (ref "37") (pin "1") (pinfunction "1_1") (pintype "passive"))
      (node (ref "C74") (pin "2") (pinfunction "2_2") (pintype "passive"))
    )
    (net (code "42") (name "Net-(*5-In_B-)") (class "Default")
      (node (ref "*5") (pin "6") (pinfunction "In_B-_6") (pintype "power_in"))
      (node (ref "33") (pin "1") (pinfunction "1_1") (pintype "passive"))
      (node (ref "34") (pin "2") (pinfunction "2_2") (pintype "passive"))
    )
    (net (code "43") (name "Net-(*5-Out_A)") (class "Default")
      (node (ref "*5") (pin "1") (pinfunction "Out_A_1") (pintype "output"))
      (node (ref "Q9") (pin "3") (pinfunction "D_3") (pintype "passive"))
    )
    (net (code "44") (name "Net-(*5-V-)") (class "Default")
      (node (ref "*5") (pin "4") (pinfunction "V-_4") (pintype "power_in"))
      (node (ref "33") (pin "2") (pinfunction "2_2") (pintype "passive"))
      (node (ref "35") (pin "2") (pinfunction "2_2") (pintype "passive"))
      (node (ref "C74") (pin "1") (pinfunction "1_1") (pintype "passive"))
    )
    (net (code "45") (name "Net-(*6-Pad5)") (class "Default")
      (node (ref "*6") (pin "5") (pinfunction "5_5") (pintype "passive"))
      (node (ref "*6") (pin "7") (pinfunction "7_7") (pintype "passive"))
      (node (ref "46") (pin "2") (pinfunction "2_2") (pintype "passive"))
    )
    (net (code "46") (name "Net-(*6-Pad6)") (class "Default")
      (node (ref "*6") (pin "6") (pinfunction "6_6") (pintype "passive"))
      (node (ref "TP14") (pin "1") (pinfunction "1_1") (pintype "passive"))
    )
    (net (code "47") (name "Net-(*6-Pad8)") (class "Default")
      (node (ref "*6") (pin "8") (pinfunction "8_8") (pintype "passive"))
      (node (ref "36") (pin "2") (pinfunction "2_2") (pintype "passive"))
      (node (ref "TP13") (pin "1") (pinfunction "1_1") (pintype "passive"))
    )
    (net (code "48") (name "Net-(8-A)") (class "Default")
      (node (ref "8") (pin "1") (pinfunction "A_1") (pintype "passive"))
      (node (ref "C44") (pin "2") (pinfunction "2_2") (pintype "passive"))
      (node (ref "C45") (pin "2") (pinfunction "2_2") (pintype "passive"))
      (node (ref "C46") (pin "2") (pinfunction "2_2") (pintype "passive"))
      (node (ref "C47") (pin "2") (pinfunction "2_2") (pintype "passive"))
      (node (ref "C48") (pin "2") (pinfunction "2_2") (pintype "passive"))
      (node (ref "C52") (pin "1") (pinfunction "1_1") (pintype "passive"))
      (node (ref "C53") (pin "1") (pinfunction "1_1") (pintype "passive"))
      (node (ref "C54") (pin "1") (pinfunction "1_1") (pintype "passive"))
      (node (ref "C55") (pin "1") (pinfunction "1_1") (pintype "passive"))
      (node (ref "C56") (pin "1") (pinfunction "1_1") (pintype "passive"))
      (node (ref "C57") (pin "1") (pinfunction "1_1") (pintype "passive"))
      (node (ref "C58") (pin "1") (pinfunction "1_1") (pintype "passive"))
      (node (ref "L4") (pin "2") (pinfunction "2_2") (pintype "passive"))
    )
    (net (code "49") (name "Net-(11-Pad1)") (class "Default")
      (node (ref "11") (pin "1") (pinfunction "1_1") (pintype "passive"))
      (node (ref "12") (pin "1") (pinfunction "1_1") (pintype "passive"))
      (node (ref "13") (pin "1") (pinfunction "1_1") (pintype "passive"))
      (node (ref "14") (pin "1") (pinfunction "1_1") (pintype "passive"))
      (node (ref "15") (pin "1") (pinfunction "1_1") (pintype "passive"))
      (node (ref "16") (pin "1") (pinfunction "1_1") (pintype "passive"))
      (node (ref "C50") (pin "2") (pinfunction "2_2") (pintype "passive"))
      (node (ref "C51") (pin "2") (pinfunction "2_2") (pintype "passive"))
      (node (ref "C60") (pin "1") (pinfunction "1_1") (pintype "passive"))
      (node (ref "H1") (pin "2") (pinfunction "2_2") (pintype "passive"))
    )
    (net (code "50") (name "Net-(18-Pad1)") (class "Default")
      (node (ref "18") (pin "1") (pinfunction "1_1") (pintype "passive"))
      (node (ref "C59") (pin "2") (pinfunction "2_2") (pintype "passive"))
    )
    (net (code "51") (name "Net-(26-Pad1)") (class "Default")
      (node (ref "26") (pin "1") (pinfunction "1_1") (pintype "passive"))
      (node (ref "29") (pin "2") (pinfunction "2_2") (pintype "passive"))
      (node (ref "C66") (pin "2") (pinfunction "2_2") (pintype "passive"))
      (node (ref "TP8") (pin "1") (pinfunction "1_1") (pintype "passive"))
    )
    (net (code "52") (name "Net-(30-Pad1)") (class "Default")
      (node (ref "30") (pin "1") (pinfunction "1_1") (pintype "passive"))
      (node (ref "C69") (pin "2") (pinfunction "2_2") (pintype "passive"))
    )
    (net (code "53") (name "Net-(30-Pad2)") (class "Default")
      (node (ref "30") (pin "2") (pinfunction "2_2") (pintype "passive"))
      (node (ref "C65") (pin "2") (pinfunction "2_2") (pintype "passive"))
      (node (ref "DE3") (pin "1") (pinfunction "1_1") (pintype "passive"))
    )
    (net (code "54") (name "Net-(36-Pad1)") (class "Default")
      (node (ref "36") (pin "1") (pinfunction "1_1") (pintype "passive"))
      (node (ref "37") (pin "2") (pinfunction "2_2") (pintype "passive"))
      (node (ref "C73") (pin "2") (pinfunction "2_2") (pintype "passive"))
    )
    (net (code "55") (name "Net-(LED6-A)") (class "Default")
      (node (ref "10") (pin "1") (pinfunction "1_1") (pintype "passive"))
      (node (ref "LED6") (pin "1") (pinfunction "A_1") (pintype "passive"))
    )
    (net (code "56") (name "Net-(LED7-A)") (class "Default")
      (node (ref "21") (pin "1") (pinfunction "1_1") (pintype "passive"))
      (node (ref "LED7") (pin "1") (pinfunction "A_1") (pintype "passive"))
    )
    (net (code "57") (name "Net-(Q6-G)") (class "Default")
      (node (ref "2") (pin "1") (pinfunction "1_1") (pintype "passive"))
      (node (ref "3") (pin "2") (pinfunction "2_2") (pintype "passive"))
      (node (ref "Q6") (pin "1") (pinfunction "G_1") (pintype "passive"))
    )
    (net (code "58") (name "Net-(Q7-G)") (class "Default")
      (node (ref "6") (pin "1") (pinfunction "1_1") (pintype "passive"))
      (node (ref "Q7") (pin "1") (pinfunction "G_1") (pintype "passive"))
    )
    (net (code "59") (name "Net-(Q8-G)") (class "Default")
      (node (ref "17") (pin "1") (pinfunction "1_1") (pintype "passive"))
      (node (ref "Q8") (pin "1") (pinfunction "G_1") (pintype "passive"))
    )
    (net (code "60") (name "Net-(Q8-S)") (class "Default")
      (node (ref "20") (pin "1") (pinfunction "1_1") (pintype "passive"))
      (node (ref "Q8") (pin "3") (pinfunction "S_3") (pintype "passive"))
      (node (ref "R68") (pin "2") (pinfunction "2_2") (pintype "passive"))
    )
    (net (code "61") (name "Net-(Q10-G)") (class "Default")
      (node (ref "44") (pin "2") (pinfunction "2_2") (pintype "passive"))
      (node (ref "45") (pin "2") (pinfunction "2_2") (pintype "passive"))
      (node (ref "Q10") (pin "1") (pinfunction "G_1") (pintype "passive"))
    )
    (net (code "62") (name "Net-(Q11-D)") (class "Default")
      (node (ref "43") (pin "1") (pinfunction "1_1") (pintype "passive"))
      (node (ref "Q11") (pin "3") (pinfunction "D_3") (pintype "passive"))
      (node (ref "Q9") (pin "1") (pinfunction "G_1") (pintype "passive"))
    )
    (net (code "63") (name "VIN") (class "Default")
      (node (ref "*2") (pin "20") (pinfunction "VIN_20") (pintype "passive"))
      (node (ref "4") (pin "2") (pinfunction "2_2") (pintype "passive"))
      (node (ref "C41") (pin "2") (pinfunction "2_2") (pintype "passive"))
    )
    (net (code "64") (name "VOUT") (class "Default")
      (node (ref "21") (pin "2") (pinfunction "2_2") (pintype "passive"))
      (node (ref "27") (pin "1") (pinfunction "1_1") (pintype "passive"))
      (node (ref "28") (pin "1") (pinfunction "1_1") (pintype "passive"))
      (node (ref "8") (pin "2") (pinfunction "K_2") (pintype "passive"))
      (node (ref "C42") (pin "2") (pinfunction "2_2") (pintype "passive"))
      (node (ref "C50") (pin "1") (pinfunction "1_1") (pintype "passive"))
      (node (ref "C51") (pin "1") (pinfunction "1_1") (pintype "passive"))
      (node (ref "H1") (pin "1") (pinfunction "1_1") (pintype "passive"))
      (node (ref "H2") (pin "1") (pinfunction "1_1") (pintype "passive"))
    )
    (net (code "65") (name "V_AMS1117_3.3V_MCU") (class "Default")
      (node (ref "*4") (pin "8") (pinfunction "VDD2_8") (pintype "power_in"))
      (node (ref "*5") (pin "8") (pinfunction "V+_8") (pintype "power_in"))
      (node (ref "*6") (pin "1") (pinfunction "1_1") (pintype "passive"))
      (node (ref "3") (pin "1") (pinfunction "1_1") (pintype "passive"))
      (node (ref "38") (pin "1") (pinfunction "1_1") (pintype "passive"))
      (node (ref "39") (pin "1") (pinfunction "1_1") (pintype "passive"))
      (node (ref "43") (pin "2") (pinfunction "2_2") (pintype "passive"))
      (node (ref "C71") (pin "1") (pinfunction "1_1") (pintype "passive"))
      (node (ref "C72") (pin "2") (pinfunction "2_2") (pintype "passive"))
      (node (ref "C75") (pin "2") (pinfunction "2_2") (pintype "passive"))
      (node (ref "C76") (pin "2") (pinfunction "2_2") (pintype "passive"))
    )
    (net (code "66") (name "V_Sourse_24V_to_BUCK") (class "Default")
      (node (ref "10") (pin "2") (pinfunction "2_2") (pintype "passive"))
      (node (ref "4") (pin "1") (pinfunction "1_1") (pintype "passive"))
      (node (ref "5") (pin "2") (pinfunction "2_2") (pintype "passive"))
      (node (ref "C33") (pin "2") (pinfunction "2_2") (pintype "passive"))
      (node (ref "C34") (pin "2") (pinfunction "2_2") (pintype "passive"))
      (node (ref "C35") (pin "2") (pinfunction "2_2") (pintype "passive"))
      (node (ref "C36") (pin "2") (pinfunction "2_2") (pintype "passive"))
      (node (ref "C37") (pin "2") (pinfunction "2_2") (pintype "passive"))
      (node (ref "C38") (pin "2") (pinfunction "2_2") (pintype "passive"))
      (node (ref "C39") (pin "2") (pinfunction "2_2") (pintype "passive"))
      (node (ref "C40") (pin "2") (pinfunction "2_2") (pintype "passive"))
      (node (ref "Q7") (pin "2") (pinfunction "D_2") (pintype "passive"))
    )
    (net (code "67") (name "V_TPS5450_5V") (class "Default")
      (node (ref "L5") (pin "2") (pinfunction "2_2") (pintype "passive"))
      (node (ref "L6") (pin "1") (pinfunction "1_1") (pintype "passive"))
    )
    (net (code "68") (name "V_TPS5450_12V") (class "Default")
      (node (ref "23") (pin "1") (pinfunction "A_1") (pintype "passive"))
      (node (ref "24") (pin "1") (pinfunction "1_1") (pintype "passive"))
    )
    (net (code "69") (name "unconnected-(SP1-Pad1)") (class "Default")
      (node (ref "SP1") (pin "1") (pinfunction "1_1") (pintype "passive"))
    )
    (net (code "70") (name "unconnected-(SP2-Pad1)") (class "Default")
      (node (ref "SP2") (pin "1") (pinfunction "1_1") (pintype "passive"))
    )
    (net (code "71") (name "unconnected-(SP3-Pad1)") (class "Default")
      (node (ref "SP3") (pin "1") (pinfunction "1_1") (pintype "passive"))
    )
    (net (code "72") (name "unconnected-(SP4-Pad1)") (class "Default")
      (node (ref "SP4") (pin "1") (pinfunction "1_1") (pintype "passive"))
    )
  )
)
